# Planter_monitor_Schematic_PCB_V1_0_0_202.net
KiCad netlist of a schematic drawn in EasyEDA
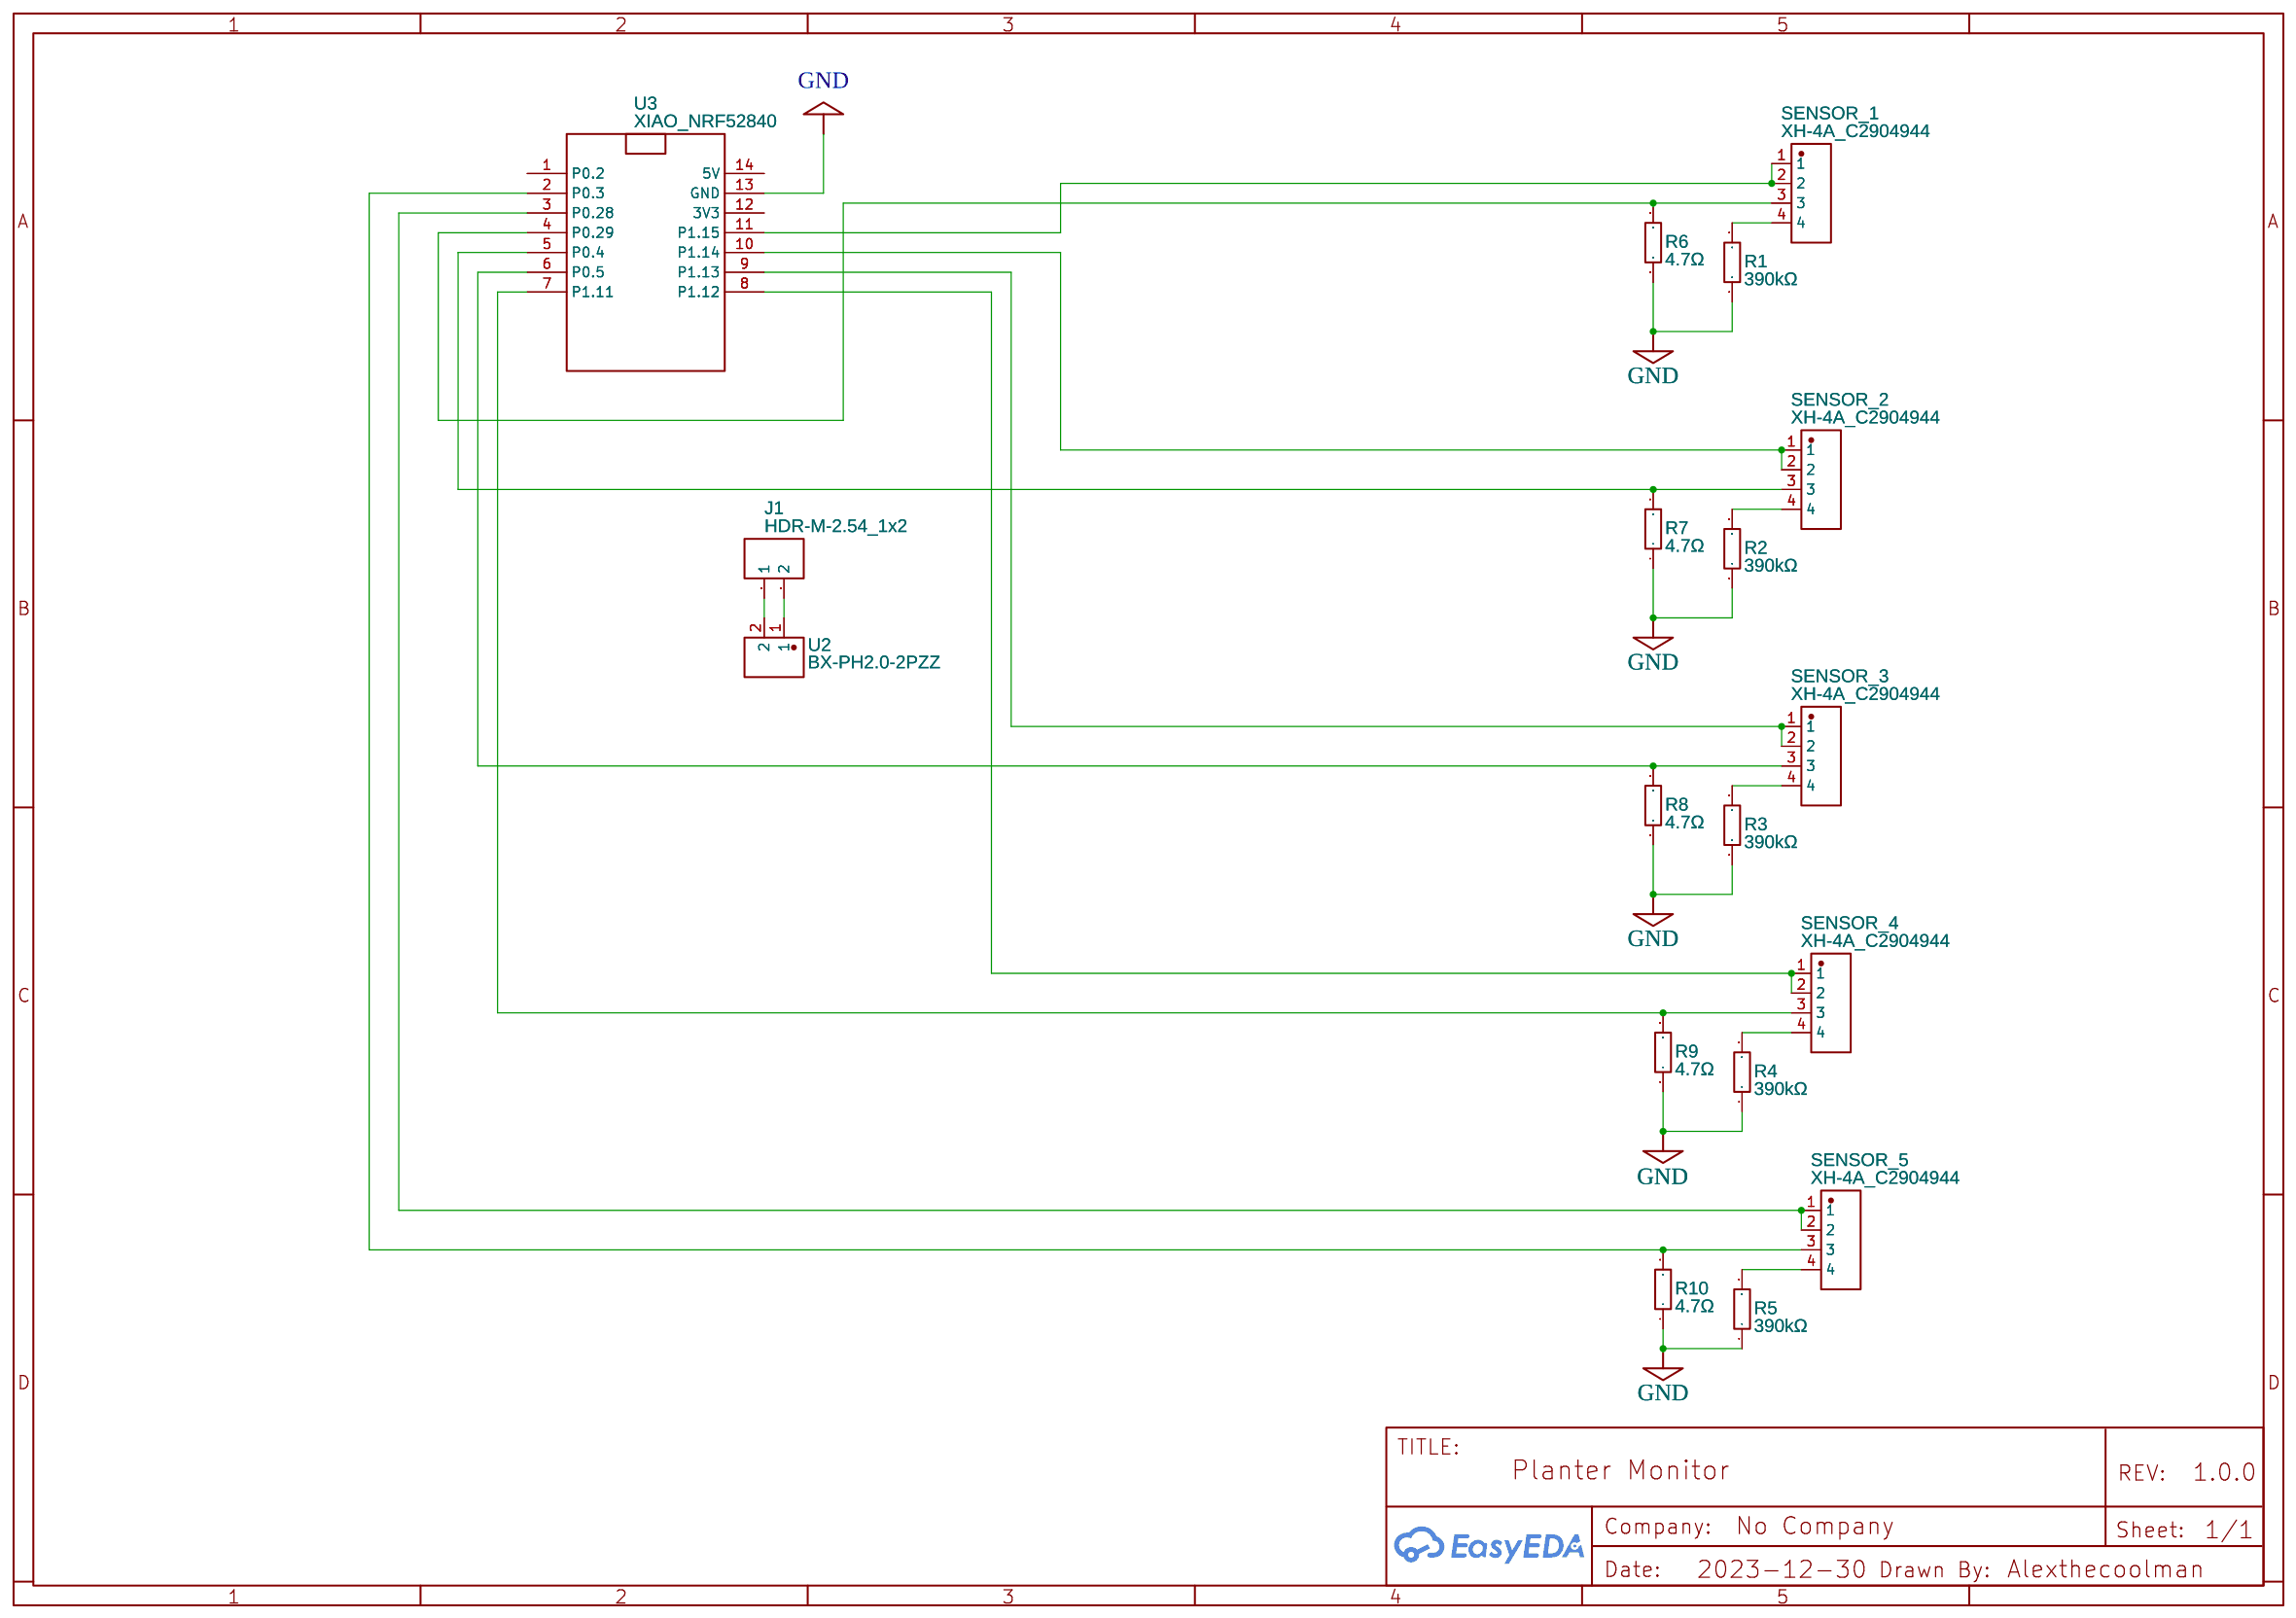
[diagram p0: schematic sheet]

(export (version "E")
  (design (tool "Eeschema 10.0.6"))
  (components
    (comp (ref "J1") (value "HDR-M-2.54_1x2") (libsource (lib "") (part "HDR-M-2.54_1x2")))
    (comp (ref "R1")
      (value "390kΩ")
      (fields
        (field (name "Manufacturer Part") "MF1/4W-390KΩ±1% T")
        (field (name "Manufacturer") "CCO(千志电子)")
      )
      (libsource (lib "") (part "MF1/4W-390KΩ±1% T52"))
    )
    (comp (ref "R2")
      (value "390kΩ")
      (fields
        (field (name "Manufacturer Part") "MF1/4W-390KΩ±1% T")
        (field (name "Manufacturer") "CCO(千志电子)")
      )
      (libsource (lib "") (part "MF1/4W-390KΩ±1% T52"))
    )
    (comp (ref "R3")
      (value "390kΩ")
      (fields
        (field (name "Manufacturer Part") "MF1/4W-390KΩ±1% T")
        (field (name "Manufacturer") "CCO(千志电子)")
      )
      (libsource (lib "") (part "MF1/4W-390KΩ±1% T52"))
    )
    (comp (ref "R4")
      (value "390kΩ")
      (fields
        (field (name "Manufacturer Part") "MF1/4W-390KΩ±1% T")
        (field (name "Manufacturer") "CCO(千志电子)")
      )
      (libsource (lib "") (part "MF1/4W-390KΩ±1% T52"))
    )
    (comp (ref "R5")
      (value "390kΩ")
      (fields
        (field (name "Manufacturer Part") "MF1/4W-390KΩ±1% T")
        (field (name "Manufacturer") "CCO(千志电子)")
      )
      (libsource (lib "") (part "MF1/4W-390KΩ±1% T52"))
    )
    (comp (ref "R6")
      (value "4.7Ω")
      (fields (field (name "Manufacturer Part") "MF1/4W-4.7Ω±1% T") (field (name "Manufacturer") "CCO(千志电子)"))
      (libsource (lib "") (part "MF1/4W-4.7Ω±1% T52"))
    )
    (comp (ref "R7")
      (value "4.7Ω")
      (fields (field (name "Manufacturer Part") "MF1/4W-4.7Ω±1% T") (field (name "Manufacturer") "CCO(千志电子)"))
      (libsource (lib "") (part "MF1/4W-4.7Ω±1% T52"))
    )
    (comp (ref "R8")
      (value "4.7Ω")
      (fields (field (name "Manufacturer Part") "MF1/4W-4.7Ω±1% T") (field (name "Manufacturer") "CCO(千志电子)"))
      (libsource (lib "") (part "MF1/4W-4.7Ω±1% T52"))
    )
    (comp (ref "R9")
      (value "4.7Ω")
      (fields (field (name "Manufacturer Part") "MF1/4W-4.7Ω±1% T") (field (name "Manufacturer") "CCO(千志电子)"))
      (libsource (lib "") (part "MF1/4W-4.7Ω±1% T52"))
    )
    (comp (ref "R10")
      (value "4.7Ω")
      (fields (field (name "Manufacturer Part") "MF1/4W-4.7Ω±1% T") (field (name "Manufacturer") "CCO(千志电子)"))
      (libsource (lib "") (part "MF1/4W-4.7Ω±1% T52"))
    )
    (comp (ref "SENSOR_1")
      (value "XH-4A_C2904944")
      (fields (field (name "Manufacturer Part") "XH-4A") (field (name "Manufacturer") "DEALON(德艺隆)"))
      (libsource (lib "") (part "XH-4A_C2904944"))
    )
    (comp (ref "SENSOR_2")
      (value "XH-4A_C2904944")
      (fields (field (name "Manufacturer Part") "XH-4A") (field (name "Manufacturer") "DEALON(德艺隆)"))
      (libsource (lib "") (part "XH-4A_C2904944"))
    )
    (comp (ref "SENSOR_3")
      (value "XH-4A_C2904944")
      (fields (field (name "Manufacturer Part") "XH-4A") (field (name "Manufacturer") "DEALON(德艺隆)"))
      (libsource (lib "") (part "XH-4A_C2904944"))
    )
    (comp (ref "SENSOR_4")
      (value "XH-4A_C2904944")
      (fields (field (name "Manufacturer Part") "XH-4A") (field (name "Manufacturer") "DEALON(德艺隆)"))
      (libsource (lib "") (part "XH-4A_C2904944"))
    )
    (comp (ref "SENSOR_5")
      (value "XH-4A_C2904944")
      (fields (field (name "Manufacturer Part") "XH-4A") (field (name "Manufacturer") "DEALON(德艺隆)"))
      (libsource (lib "") (part "XH-4A_C2904944"))
    )
    (comp (ref "U2")
      (value "BX-PH2.0-2PZZ")
      (fields (field (name "Manufacturer") "Bossie(博锡)"))
      (libsource (lib "") (part "BX-PH2.0-2PZZ"))
    )
    (comp (ref "U3") (value "XIAO_NRF52840") (libsource (lib "") (part "XIAO_NRF52840 [ARCTURUS]")))
  )
  (nets
    (net (code "1") (name "GND") (class "Default")
      (node (ref "R1") (pin "1") (pinfunction "1_1") (pintype "unspecified"))
      (node (ref "R10") (pin "1") (pinfunction "1_1") (pintype "unspecified"))
      (node (ref "R2") (pin "1") (pinfunction "1_1") (pintype "unspecified"))
      (node (ref "R3") (pin "1") (pinfunction "1_1") (pintype "unspecified"))
      (node (ref "R4") (pin "1") (pinfunction "1_1") (pintype "unspecified"))
      (node (ref "R5") (pin "1") (pinfunction "1_1") (pintype "unspecified"))
      (node (ref "R6") (pin "1") (pinfunction "1_1") (pintype "unspecified"))
      (node (ref "R7") (pin "1") (pinfunction "1_1") (pintype "unspecified"))
      (node (ref "R8") (pin "1") (pinfunction "1_1") (pintype "unspecified"))
      (node (ref "R9") (pin "1") (pinfunction "1_1") (pintype "unspecified"))
      (node (ref "U3") (pin "13") (pinfunction "GND_13") (pintype "unspecified"))
    )
    (net (code "2") (name "Net-(J1-Pad1)") (class "Default")
      (node (ref "J1") (pin "1") (pinfunction "1_1") (pintype "unspecified"))
      (node (ref "U2") (pin "2") (pinfunction "2_2") (pintype "unspecified"))
    )
    (net (code "3") (name "Net-(J1-Pad2)") (class "Default")
      (node (ref "J1") (pin "2") (pinfunction "2_2") (pintype "unspecified"))
      (node (ref "U2") (pin "1") (pinfunction "1_1") (pintype "unspecified"))
    )
    (net (code "4") (name "Net-(R1-Pad2)") (class "Default")
      (node (ref "R1") (pin "2") (pinfunction "2_2") (pintype "unspecified"))
      (node (ref "SENSOR_1") (pin "4") (pinfunction "4_4") (pintype "unspecified"))
    )
    (net (code "5") (name "Net-(R2-Pad2)") (class "Default")
      (node (ref "R2") (pin "2") (pinfunction "2_2") (pintype "unspecified"))
      (node (ref "SENSOR_2") (pin "4") (pinfunction "4_4") (pintype "unspecified"))
    )
    (net (code "6") (name "Net-(R3-Pad2)") (class "Default")
      (node (ref "R3") (pin "2") (pinfunction "2_2") (pintype "unspecified"))
      (node (ref "SENSOR_3") (pin "4") (pinfunction "4_4") (pintype "unspecified"))
    )
    (net (code "7") (name "Net-(R4-Pad2)") (class "Default")
      (node (ref "R4") (pin "2") (pinfunction "2_2") (pintype "unspecified"))
      (node (ref "SENSOR_4") (pin "4") (pinfunction "4_4") (pintype "unspecified"))
    )
    (net (code "8") (name "Net-(R5-Pad2)") (class "Default")
      (node (ref "R5") (pin "2") (pinfunction "2_2") (pintype "unspecified"))
      (node (ref "SENSOR_5") (pin "4") (pinfunction "4_4") (pintype "unspecified"))
    )
    (net (code "9") (name "Net-(U3-P0.3)") (class "Default")
      (node (ref "R10") (pin "2") (pinfunction "2_2") (pintype "unspecified"))
      (node (ref "SENSOR_5") (pin "3") (pinfunction "3_3") (pintype "unspecified"))
      (node (ref "U3") (pin "2") (pinfunction "P0.3_2") (pintype "unspecified"))
    )
    (net (code "10") (name "Net-(U3-P0.4)") (class "Default")
      (node (ref "R7") (pin "2") (pinfunction "2_2") (pintype "unspecified"))
      (node (ref "SENSOR_2") (pin "3") (pinfunction "3_3") (pintype "unspecified"))
      (node (ref "U3") (pin "5") (pinfunction "P0.4_5") (pintype "unspecified"))
    )
    (net (code "11") (name "Net-(U3-P0.5)") (class "Default")
      (node (ref "R8") (pin "2") (pinfunction "2_2") (pintype "unspecified"))
      (node (ref "SENSOR_3") (pin "3") (pinfunction "3_3") (pintype "unspecified"))
      (node (ref "U3") (pin "6") (pinfunction "P0.5_6") (pintype "unspecified"))
    )
    (net (code "12") (name "Net-(U3-P0.28)") (class "Default")
      (node (ref "SENSOR_5") (pin "1") (pinfunction "1_1") (pintype "unspecified"))
      (node (ref "SENSOR_5") (pin "2") (pinfunction "2_2") (pintype "unspecified"))
      (node (ref "U3") (pin "3") (pinfunction "P0.28_3") (pintype "unspecified"))
    )
    (net (code "13") (name "Net-(U3-P0.29)") (class "Default")
      (node (ref "R6") (pin "2") (pinfunction "2_2") (pintype "unspecified"))
      (node (ref "SENSOR_1") (pin "3") (pinfunction "3_3") (pintype "unspecified"))
      (node (ref "U3") (pin "4") (pinfunction "P0.29_4") (pintype "unspecified"))
    )
    (net (code "14") (name "Net-(U3-P1.11)") (class "Default")
      (node (ref "R9") (pin "2") (pinfunction "2_2") (pintype "unspecified"))
      (node (ref "SENSOR_4") (pin "3") (pinfunction "3_3") (pintype "unspecified"))
      (node (ref "U3") (pin "7") (pinfunction "P1.11_7") (pintype "unspecified"))
    )
    (net (code "15") (name "Net-(U3-P1.12)") (class "Default")
      (node (ref "SENSOR_4") (pin "1") (pinfunction "1_1") (pintype "unspecified"))
      (node (ref "SENSOR_4") (pin "2") (pinfunction "2_2") (pintype "unspecified"))
      (node (ref "U3") (pin "8") (pinfunction "P1.12_8") (pintype "unspecified"))
    )
    (net (code "16") (name "Net-(U3-P1.13)") (class "Default")
      (node (ref "SENSOR_3") (pin "1") (pinfunction "1_1") (pintype "unspecified"))
      (node (ref "SENSOR_3") (pin "2") (pinfunction "2_2") (pintype "unspecified"))
      (node (ref "U3") (pin "9") (pinfunction "P1.13_9") (pintype "unspecified"))
    )
    (net (code "17") (name "Net-(U3-P1.14)") (class "Default")
      (node (ref "SENSOR_2") (pin "1") (pinfunction "1_1") (pintype "unspecified"))
      (node (ref "SENSOR_2") (pin "2") (pinfunction "2_2") (pintype "unspecified"))
      (node (ref "U3") (pin "10") (pinfunction "P1.14_10") (pintype "unspecified"))
    )
    (net (code "18") (name "Net-(U3-P1.15)") (class "Default")
      (node (ref "SENSOR_1") (pin "1") (pinfunction "1_1") (pintype "unspecified"))
      (node (ref "SENSOR_1") (pin "2") (pinfunction "2_2") (pintype "unspecified"))
      (node (ref "U3") (pin "11") (pinfunction "P1.15_11") (pintype "unspecified"))
    )
    (net (code "19") (name "unconnected-(U3-3V3-Pad12)") (class "Default")
      (node (ref "U3") (pin "12") (pinfunction "3V3_12") (pintype "unspecified"))
    )
    (net (code "20") (name "unconnected-(U3-5V-Pad14)") (class "Default")
      (node (ref "U3") (pin "14") (pinfunction "5V_14") (pintype "unspecified"))
    )
    (net (code "21") (name "unconnected-(U3-P0.2-Pad1)") (class "Default")
      (node (ref "U3") (pin "1") (pinfunction "P0.2_1") (pintype "unspecified"))
    )
  )
)
